# OPEN_SPECTRO_PI_HAT.net
KiCad netlist of a schematic drawn in EAGLE
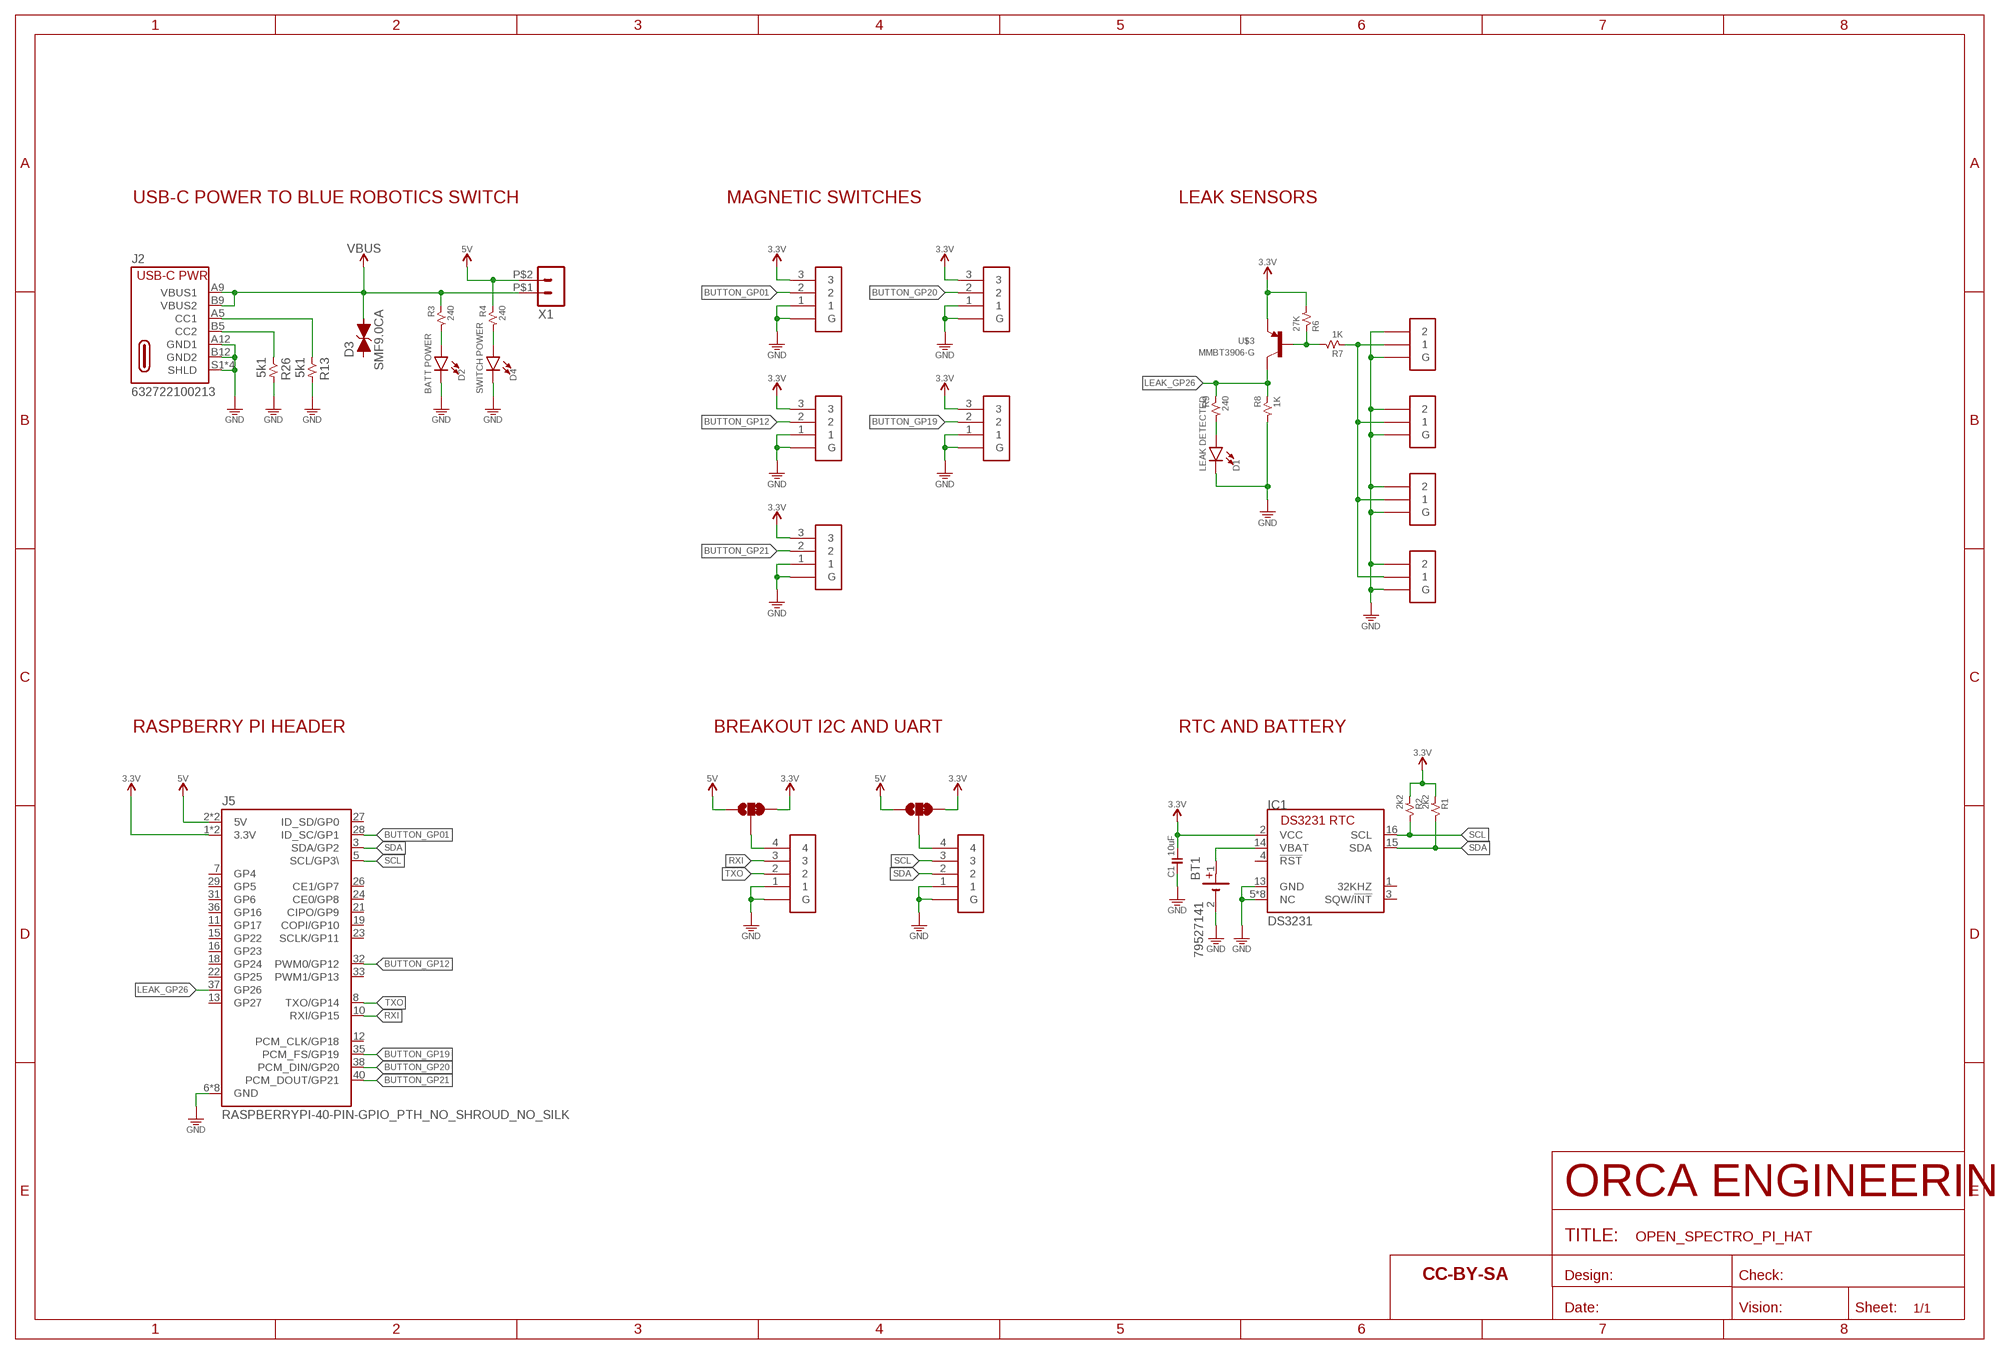
[diagram p0: schematic, sheet 1]

(export (version "E")
  (design (tool "Eeschema 10.0.6"))
  (components
    (comp (ref "BT1")
      (value "79527141")
      (footprint "eagle-import:79527141")
      (fields
        (field (name "DIGIKEY_PART_NO") "732-12325-2-ND")
        (field (name "MANUFACTURER") "Wurth Electronics Inc.")
        (field (name "CREATED_BY") "PCBLayout.com")
      )
      (libsource (lib "eagle-import") (part "79527141"))
    )
    (comp (ref "C1")
      (value "10uF")
      (footprint "eagle-import:0805")
      (libsource (lib "eagle-import") (part "0805"))
    )
    (comp (ref "D1")
      (value "LEAK DETECTED")
      (footprint "eagle-import:0805_LED")
      (libsource (lib "eagle-import") (part "LED0805"))
    )
    (comp (ref "D2")
      (value "BATT POWER")
      (footprint "eagle-import:0805_LED")
      (libsource (lib "eagle-import") (part "LED0805"))
    )
    (comp (ref "D3")
      (value "SMF9.0CA")
      (footprint "eagle-import:SOD-123F-TVS")
      (libsource (lib "eagle-import") (part "DIODE-TVS-BIDIRECTIONALSMF18CA"))
    )
    (comp (ref "D4")
      (value "SWITCH POWER")
      (footprint "eagle-import:0805_LED")
      (libsource (lib "eagle-import") (part "LED0805"))
    )
    (comp (ref "IC1")
      (value "DS3231/SO")
      (footprint "eagle-import:SO16W")
      (libsource (lib "eagle-import") (part "DS3231/SO"))
    )
    (comp (ref "J2")
      (value "632722100213")
      (footprint "eagle-import:632722100213")
      (libsource (lib "eagle-import") (part "USB-C_PWR_6_PIN"))
    )
    (comp (ref "J5")
      (value "RASPBERRYPI-40-PIN-GPIO_PTH_NO_SHROUD_NO_SILK")
      (footprint "eagle-import:2X20_NOSILK")
      (libsource (lib "eagle-import") (part "RASPBERRYPI-40-PIN-GPIO_PTH_NO_SHROUD_NO_SILK"))
    )
    (comp (ref "JP1")
      (value "JUMPER-SMT_3_1-NC_TRACE_SILK")
      (footprint "eagle-import:SMT-JUMPER_3_1-NC_TRACE_SILK")
      (libsource (lib "eagle-import") (part "JUMPER-SMT_3_1-NC_TRACE_SILK"))
    )
    (comp (ref "JP2")
      (value "JUMPER-SMT_3_1-NC_TRACE_SILK")
      (footprint "eagle-import:SMT-JUMPER_3_1-NC_TRACE_SILK")
      (libsource (lib "eagle-import") (part "JUMPER-SMT_3_1-NC_TRACE_SILK"))
    )
    (comp (ref "R1")
      (value "2k2")
      (footprint "eagle-import:0805")
      (libsource (lib "eagle-import") (part "_L_Resistors_vf.673Dwt_LQuWdsXra6AjxcA_0805"))
    )
    (comp (ref "R2")
      (value "2k2")
      (footprint "eagle-import:0805")
      (libsource (lib "eagle-import") (part "_L_Resistors_vf.673Dwt_LQuWdsXra6AjxcA_0805"))
    )
    (comp (ref "R3")
      (value "240")
      (footprint "eagle-import:0805")
      (libsource (lib "eagle-import") (part "_L_Resistors_vf.673Dwt_LQuWdsXra6AjxcA_0805"))
    )
    (comp (ref "R4")
      (value "240")
      (footprint "eagle-import:0805")
      (libsource (lib "eagle-import") (part "_L_Resistors_vf.673Dwt_LQuWdsXra6AjxcA_0805"))
    )
    (comp (ref "R6")
      (value "27K")
      (footprint "eagle-import:0805")
      (libsource (lib "eagle-import") (part "_L_Resistors_vf.673Dwt_LQuWdsXra6AjxcA_0805"))
    )
    (comp (ref "R7")
      (value "1K")
      (footprint "eagle-import:0805")
      (libsource (lib "eagle-import") (part "_L_Resistors_vf.673Dwt_LQuWdsXra6AjxcA_0805"))
    )
    (comp (ref "R8")
      (value "1K")
      (footprint "eagle-import:0805")
      (libsource (lib "eagle-import") (part "_L_Resistors_vf.673Dwt_LQuWdsXra6AjxcA_0805"))
    )
    (comp (ref "R9")
      (value "240")
      (footprint "eagle-import:0805")
      (libsource (lib "eagle-import") (part "_L_Resistors_vf.673Dwt_LQuWdsXra6AjxcA_0805"))
    )
    (comp (ref "R13")
      (value "5k1")
      (footprint "eagle-import:0805")
      (libsource (lib "eagle-import") (part "_L_Resistors_vf.673Dwt_LQuWdsXra6AjxcA_0805"))
    )
    (comp (ref "R26")
      (value "5k1")
      (footprint "eagle-import:0805")
      (libsource (lib "eagle-import") (part "_L_Resistors_vf.673Dwt_LQuWdsXra6AjxcA_0805"))
    )
    (comp (ref "U$1")
      (value "JST-GH-2SIDE")
      (footprint "eagle-import:JST-GH-SIDE-2")
      (libsource (lib "eagle-import") (part "JST-GH-2SIDE"))
    )
    (comp (ref "U$2")
      (value "JST-GH-2SIDE")
      (footprint "eagle-import:JST-GH-SIDE-2")
      (libsource (lib "eagle-import") (part "JST-GH-2SIDE"))
    )
    (comp (ref "U$3")
      (value "MMBT3906-G")
      (footprint "eagle-import:SOT23-3_GENERIC")
      (libsource (lib "eagle-import") (part "TRANS_PNPMMBT3906-G"))
    )
    (comp (ref "U$4")
      (value "JST-GH-3SIDE")
      (footprint "eagle-import:JST-GH-SIDE-3")
      (libsource (lib "eagle-import") (part "JST-GH-3SIDE"))
    )
    (comp (ref "U$5")
      (value "JST-GH-2SIDE")
      (footprint "eagle-import:JST-GH-SIDE-2")
      (libsource (lib "eagle-import") (part "JST-GH-2SIDE"))
    )
    (comp (ref "U$6")
      (value "JST-GH-2SIDE")
      (footprint "eagle-import:JST-GH-SIDE-2")
      (libsource (lib "eagle-import") (part "JST-GH-2SIDE"))
    )
    (comp (ref "U$7")
      (value "JST-GH-4SIDE")
      (footprint "eagle-import:JST-GH-SIDE-4")
      (libsource (lib "eagle-import") (part "JST-GH-4SIDE"))
    )
    (comp (ref "U$8")
      (value "JST-GH-4SIDE")
      (footprint "eagle-import:JST-GH-SIDE-4")
      (libsource (lib "eagle-import") (part "JST-GH-4SIDE"))
    )
    (comp (ref "U$11")
      (value "JST-GH-3SIDE")
      (footprint "eagle-import:JST-GH-SIDE-3")
      (libsource (lib "eagle-import") (part "JST-GH-3SIDE"))
    )
    (comp (ref "U$12")
      (value "JST-GH-3SIDE")
      (footprint "eagle-import:JST-GH-SIDE-3")
      (libsource (lib "eagle-import") (part "JST-GH-3SIDE"))
    )
    (comp (ref "U$14")
      (value "JST-GH-3SIDE")
      (footprint "eagle-import:JST-GH-SIDE-3")
      (libsource (lib "eagle-import") (part "JST-GH-3SIDE"))
    )
    (comp (ref "U$15")
      (value "JST-GH-3SIDE")
      (footprint "eagle-import:JST-GH-SIDE-3")
      (libsource (lib "eagle-import") (part "JST-GH-3SIDE"))
    )
    (comp (ref "X1")
      (value "MICRO-FIT_02P43650-0200")
      (footprint "eagle-import:43650-0200")
      (libsource (lib "eagle-import") (part "MICRO-FIT_02P43650-0200"))
    )
  )
  (nets
    (net (code "1") (name "3.3V") (class "Default")
      (node (ref "C1") (pin "1") (pinfunction "1_1") (pintype "passive"))
      (node (ref "IC1") (pin "2") (pinfunction "VCC_2") (pintype "power_in"))
      (node (ref "J5") (pin "1") (pinfunction "3.3V_1") (pintype "power_in"))
      (node (ref "J5") (pin "17") (pinfunction "3.3V_17") (pintype "power_in"))
      (node (ref "JP1") (pin "3") (pinfunction "3_3") (pintype "passive"))
      (node (ref "JP2") (pin "3") (pinfunction "3_3") (pintype "passive"))
      (node (ref "R1") (pin "2") (pinfunction "2_2") (pintype "passive"))
      (node (ref "R2") (pin "2") (pinfunction "2_2") (pintype "passive"))
      (node (ref "R6") (pin "2") (pinfunction "2_2") (pintype "passive"))
      (node (ref "U$11") (pin "3") (pinfunction "3_3") (pintype "bidirectional"))
      (node (ref "U$12") (pin "3") (pinfunction "3_3") (pintype "bidirectional"))
      (node (ref "U$14") (pin "3") (pinfunction "3_3") (pintype "bidirectional"))
      (node (ref "U$15") (pin "3") (pinfunction "3_3") (pintype "bidirectional"))
      (node (ref "U$3") (pin "3") (pinfunction "C_3") (pintype "passive"))
      (node (ref "U$4") (pin "3") (pinfunction "3_3") (pintype "bidirectional"))
    )
    (net (code "2") (name "5V") (class "Default")
      (node (ref "J5") (pin "2") (pinfunction "5V_2") (pintype "power_in"))
      (node (ref "J5") (pin "4") (pinfunction "5V_4") (pintype "power_in"))
      (node (ref "JP1") (pin "1") (pinfunction "1_1") (pintype "passive"))
      (node (ref "JP2") (pin "1") (pinfunction "1_1") (pintype "passive"))
      (node (ref "R4") (pin "1") (pinfunction "1_1") (pintype "passive"))
      (node (ref "X1") (pin "P$2") (pinfunction "2_P$2") (pintype "passive"))
    )
    (net (code "3") (name "BUTTON_GP01") (class "Default")
      (node (ref "J5") (pin "28") (pinfunction "ID_SC/GP1_28") (pintype "bidirectional"))
      (node (ref "U$4") (pin "2") (pinfunction "2_2") (pintype "bidirectional"))
    )
    (net (code "4") (name "BUTTON_GP12") (class "Default")
      (node (ref "J5") (pin "32") (pinfunction "PWM0/GP12_32") (pintype "bidirectional"))
      (node (ref "U$11") (pin "2") (pinfunction "2_2") (pintype "bidirectional"))
    )
    (net (code "5") (name "BUTTON_GP19") (class "Default")
      (node (ref "J5") (pin "35") (pinfunction "PCM_FS/GP19_35") (pintype "bidirectional"))
      (node (ref "U$15") (pin "2") (pinfunction "2_2") (pintype "bidirectional"))
    )
    (net (code "6") (name "BUTTON_GP20") (class "Default")
      (node (ref "J5") (pin "38") (pinfunction "PCM_DIN/GP20_38") (pintype "bidirectional"))
      (node (ref "U$14") (pin "2") (pinfunction "2_2") (pintype "bidirectional"))
    )
    (net (code "7") (name "BUTTON_GP21") (class "Default")
      (node (ref "J5") (pin "40") (pinfunction "PCM_DOUT/GP21_40") (pintype "bidirectional"))
      (node (ref "U$12") (pin "2") (pinfunction "2_2") (pintype "bidirectional"))
    )
    (net (code "8") (name "GND") (class "Default")
      (node (ref "BT1") (pin "2") (pinfunction "-_2") (pintype "passive"))
      (node (ref "C1") (pin "2") (pinfunction "2_2") (pintype "passive"))
      (node (ref "D1") (pin "C") (pinfunction "C_C") (pintype "passive"))
      (node (ref "D2") (pin "C") (pinfunction "C_C") (pintype "passive"))
      (node (ref "D4") (pin "C") (pinfunction "C_C") (pintype "passive"))
      (node (ref "IC1") (pin "10") (pinfunction "NC_10") (pintype "power_in"))
      (node (ref "IC1") (pin "11") (pinfunction "NC_11") (pintype "power_in"))
      (node (ref "IC1") (pin "12") (pinfunction "NC_12") (pintype "power_in"))
      (node (ref "IC1") (pin "13") (pinfunction "GND_13") (pintype "power_in"))
      (node (ref "IC1") (pin "5") (pinfunction "NC_5") (pintype "power_in"))
      (node (ref "IC1") (pin "6") (pinfunction "NC_6") (pintype "power_in"))
      (node (ref "IC1") (pin "7") (pinfunction "NC_7") (pintype "power_in"))
      (node (ref "IC1") (pin "8") (pinfunction "NC_8") (pintype "power_in"))
      (node (ref "IC1") (pin "9") (pinfunction "NC_9") (pintype "power_in"))
      (node (ref "J2") (pin "A12") (pinfunction "GND1_A12") (pintype "passive"))
      (node (ref "J2") (pin "B12") (pinfunction "GND2_B12") (pintype "passive"))
      (node (ref "J2") (pin "S1") (pinfunction "SHLD_S1") (pintype "passive"))
      (node (ref "J2") (pin "S2") (pinfunction "SHLD_S2") (pintype "passive"))
      (node (ref "J2") (pin "S3") (pinfunction "SHLD_S3") (pintype "passive"))
      (node (ref "J2") (pin "S4") (pinfunction "SHLD_S4") (pintype "passive"))
      (node (ref "J5") (pin "14") (pinfunction "GND_14") (pintype "power_in"))
      (node (ref "J5") (pin "20") (pinfunction "GND_20") (pintype "power_in"))
      (node (ref "J5") (pin "25") (pinfunction "GND_25") (pintype "power_in"))
      (node (ref "J5") (pin "30") (pinfunction "GND_30") (pintype "power_in"))
      (node (ref "J5") (pin "34") (pinfunction "GND_34") (pintype "power_in"))
      (node (ref "J5") (pin "39") (pinfunction "GND_39") (pintype "power_in"))
      (node (ref "J5") (pin "6") (pinfunction "GND_6") (pintype "power_in"))
      (node (ref "J5") (pin "9") (pinfunction "GND_9") (pintype "power_in"))
      (node (ref "R13") (pin "2") (pinfunction "2_2") (pintype "passive"))
      (node (ref "R26") (pin "2") (pinfunction "2_2") (pintype "passive"))
      (node (ref "R8") (pin "2") (pinfunction "2_2") (pintype "passive"))
      (node (ref "U$1") (pin "2") (pinfunction "2_2") (pintype "bidirectional"))
      (node (ref "U$1") (pin "MECH1") (pinfunction "G_MECH1") (pintype "bidirectional"))
      (node (ref "U$1") (pin "MECH2") (pinfunction "G_MECH2") (pintype "bidirectional"))
      (node (ref "U$11") (pin "1") (pinfunction "1_1") (pintype "bidirectional"))
      (node (ref "U$11") (pin "MECH1") (pinfunction "G_MECH1") (pintype "bidirectional"))
      (node (ref "U$11") (pin "MECH2") (pinfunction "G_MECH2") (pintype "bidirectional"))
      (node (ref "U$12") (pin "1") (pinfunction "1_1") (pintype "bidirectional"))
      (node (ref "U$12") (pin "MECH1") (pinfunction "G_MECH1") (pintype "bidirectional"))
      (node (ref "U$12") (pin "MECH2") (pinfunction "G_MECH2") (pintype "bidirectional"))
      (node (ref "U$14") (pin "1") (pinfunction "1_1") (pintype "bidirectional"))
      (node (ref "U$14") (pin "MECH1") (pinfunction "G_MECH1") (pintype "bidirectional"))
      (node (ref "U$14") (pin "MECH2") (pinfunction "G_MECH2") (pintype "bidirectional"))
      (node (ref "U$15") (pin "1") (pinfunction "1_1") (pintype "bidirectional"))
      (node (ref "U$15") (pin "MECH1") (pinfunction "G_MECH1") (pintype "bidirectional"))
      (node (ref "U$15") (pin "MECH2") (pinfunction "G_MECH2") (pintype "bidirectional"))
      (node (ref "U$2") (pin "2") (pinfunction "2_2") (pintype "bidirectional"))
      (node (ref "U$2") (pin "MECH1") (pinfunction "G_MECH1") (pintype "bidirectional"))
      (node (ref "U$2") (pin "MECH2") (pinfunction "G_MECH2") (pintype "bidirectional"))
      (node (ref "U$4") (pin "1") (pinfunction "1_1") (pintype "bidirectional"))
      (node (ref "U$4") (pin "MECH1") (pinfunction "G_MECH1") (pintype "bidirectional"))
      (node (ref "U$4") (pin "MECH2") (pinfunction "G_MECH2") (pintype "bidirectional"))
      (node (ref "U$5") (pin "2") (pinfunction "2_2") (pintype "bidirectional"))
      (node (ref "U$5") (pin "MECH1") (pinfunction "G_MECH1") (pintype "bidirectional"))
      (node (ref "U$5") (pin "MECH2") (pinfunction "G_MECH2") (pintype "bidirectional"))
      (node (ref "U$6") (pin "2") (pinfunction "2_2") (pintype "bidirectional"))
      (node (ref "U$6") (pin "MECH1") (pinfunction "G_MECH1") (pintype "bidirectional"))
      (node (ref "U$6") (pin "MECH2") (pinfunction "G_MECH2") (pintype "bidirectional"))
      (node (ref "U$7") (pin "1") (pinfunction "1_1") (pintype "bidirectional"))
      (node (ref "U$7") (pin "MECH1") (pinfunction "G_MECH1") (pintype "bidirectional"))
      (node (ref "U$7") (pin "MECH2") (pinfunction "G_MECH2") (pintype "bidirectional"))
      (node (ref "U$8") (pin "1") (pinfunction "1_1") (pintype "bidirectional"))
      (node (ref "U$8") (pin "MECH1") (pinfunction "G_MECH1") (pintype "bidirectional"))
      (node (ref "U$8") (pin "MECH2") (pinfunction "G_MECH2") (pintype "bidirectional"))
    )
    (net (code "9") (name "LEAK_GP26") (class "Default")
      (node (ref "J5") (pin "37") (pinfunction "GP26_37") (pintype "bidirectional"))
      (node (ref "R8") (pin "1") (pinfunction "1_1") (pintype "passive"))
      (node (ref "R9") (pin "1") (pinfunction "1_1") (pintype "passive"))
      (node (ref "U$3") (pin "2") (pinfunction "E_2") (pintype "passive"))
    )
    (net (code "10") (name "Net-(BT1-+)") (class "Default")
      (node (ref "BT1") (pin "1") (pinfunction "+_1") (pintype "passive"))
      (node (ref "IC1") (pin "14") (pinfunction "VBAT_14") (pintype "power_in"))
    )
    (net (code "11") (name "Net-(D1-PadA)") (class "Default")
      (node (ref "D1") (pin "A") (pinfunction "A_A") (pintype "passive"))
      (node (ref "R9") (pin "2") (pinfunction "2_2") (pintype "passive"))
    )
    (net (code "12") (name "Net-(D2-PadA)") (class "Default")
      (node (ref "D2") (pin "A") (pinfunction "A_A") (pintype "passive"))
      (node (ref "R3") (pin "2") (pinfunction "2_2") (pintype "passive"))
    )
    (net (code "13") (name "Net-(D4-PadA)") (class "Default")
      (node (ref "D4") (pin "A") (pinfunction "A_A") (pintype "passive"))
      (node (ref "R4") (pin "2") (pinfunction "2_2") (pintype "passive"))
    )
    (net (code "14") (name "Net-(J2-CC1)") (class "Default")
      (node (ref "J2") (pin "A5") (pinfunction "CC1_A5") (pintype "passive"))
      (node (ref "R13") (pin "1") (pinfunction "1_1") (pintype "passive"))
    )
    (net (code "15") (name "Net-(J2-CC2)") (class "Default")
      (node (ref "J2") (pin "B5") (pinfunction "CC2_B5") (pintype "passive"))
      (node (ref "R26") (pin "1") (pinfunction "1_1") (pintype "passive"))
    )
    (net (code "16") (name "Net-(JP1-Pad2)") (class "Default")
      (node (ref "JP1") (pin "2") (pinfunction "2_2") (pintype "passive"))
      (node (ref "U$7") (pin "4") (pinfunction "4_4") (pintype "bidirectional"))
    )
    (net (code "17") (name "Net-(JP2-Pad2)") (class "Default")
      (node (ref "JP2") (pin "2") (pinfunction "2_2") (pintype "passive"))
      (node (ref "U$8") (pin "4") (pinfunction "4_4") (pintype "bidirectional"))
    )
    (net (code "18") (name "Net-(R7-Pad2)") (class "Default")
      (node (ref "R7") (pin "2") (pinfunction "2_2") (pintype "passive"))
      (node (ref "U$1") (pin "1") (pinfunction "1_1") (pintype "bidirectional"))
      (node (ref "U$2") (pin "1") (pinfunction "1_1") (pintype "bidirectional"))
      (node (ref "U$5") (pin "1") (pinfunction "1_1") (pintype "bidirectional"))
      (node (ref "U$6") (pin "1") (pinfunction "1_1") (pintype "bidirectional"))
    )
    (net (code "19") (name "Net-(U$3-B)") (class "Default")
      (node (ref "R6") (pin "1") (pinfunction "1_1") (pintype "passive"))
      (node (ref "R7") (pin "1") (pinfunction "1_1") (pintype "passive"))
      (node (ref "U$3") (pin "1") (pinfunction "B_1") (pintype "passive"))
    )
    (net (code "20") (name "RXI") (class "Default")
      (node (ref "J5") (pin "10") (pinfunction "RXI/GP15_10") (pintype "input"))
      (node (ref "U$8") (pin "3") (pinfunction "3_3") (pintype "bidirectional"))
    )
    (net (code "21") (name "SCL") (class "Default")
      (node (ref "IC1") (pin "16") (pinfunction "SCL_16") (pintype "bidirectional"))
      (node (ref "J5") (pin "5") (pinfunction "SCL/GP3\\_5") (pintype "bidirectional"))
      (node (ref "R2") (pin "1") (pinfunction "1_1") (pintype "passive"))
      (node (ref "U$7") (pin "3") (pinfunction "3_3") (pintype "bidirectional"))
    )
    (net (code "22") (name "SDA") (class "Default")
      (node (ref "IC1") (pin "15") (pinfunction "SDA_15") (pintype "bidirectional"))
      (node (ref "J5") (pin "3") (pinfunction "SDA/GP2_3") (pintype "bidirectional"))
      (node (ref "R1") (pin "1") (pinfunction "1_1") (pintype "passive"))
      (node (ref "U$7") (pin "2") (pinfunction "2_2") (pintype "bidirectional"))
    )
    (net (code "23") (name "TXO") (class "Default")
      (node (ref "J5") (pin "8") (pinfunction "TXO/GP14_8") (pintype "output"))
      (node (ref "U$8") (pin "2") (pinfunction "2_2") (pintype "bidirectional"))
    )
    (net (code "24") (name "VBUS") (class "Default")
      (node (ref "D3") (pin "C") (pinfunction "C2_C") (pintype "passive"))
      (node (ref "J2") (pin "A9") (pinfunction "VBUS1_A9") (pintype "passive"))
      (node (ref "J2") (pin "B9") (pinfunction "VBUS2_B9") (pintype "passive"))
      (node (ref "R3") (pin "1") (pinfunction "1_1") (pintype "passive"))
      (node (ref "X1") (pin "P$1") (pinfunction "1_P$1") (pintype "passive"))
    )
    (net (code "25") (name "unconnected-(D3-C1-PadA)") (class "Default")
      (node (ref "D3") (pin "A") (pinfunction "C1_A") (pintype "passive"))
    )
    (net (code "26") (name "unconnected-(IC1-32KHZ-Pad1)") (class "Default")
      (node (ref "IC1") (pin "1") (pinfunction "32KHZ_1") (pintype "output"))
    )
    (net (code "27") (name "unconnected-(IC1-SQW{slash}~{INT}-Pad3)") (class "Default")
      (node (ref "IC1") (pin "3") (pinfunction "SQW/~{INT}_3") (pintype "output"))
    )
    (net (code "28") (name "unconnected-(IC1-~{RST}-Pad4)") (class "Default")
      (node (ref "IC1") (pin "4") (pinfunction "~{RST}_4") (pintype "bidirectional"))
    )
    (net (code "29") (name "unconnected-(J5-CE0{slash}GP8-Pad24)") (class "Default")
      (node (ref "J5") (pin "24") (pinfunction "CE0/GP8_24") (pintype "output"))
    )
    (net (code "30") (name "unconnected-(J5-CE1{slash}GP7-Pad26)") (class "Default")
      (node (ref "J5") (pin "26") (pinfunction "CE1/GP7_26") (pintype "output"))
    )
    (net (code "31") (name "unconnected-(J5-CIPO{slash}GP9-Pad21)") (class "Default")
      (node (ref "J5") (pin "21") (pinfunction "CIPO/GP9_21") (pintype "input"))
    )
    (net (code "32") (name "unconnected-(J5-COPI{slash}GP10-Pad19)") (class "Default")
      (node (ref "J5") (pin "19") (pinfunction "COPI/GP10_19") (pintype "output"))
    )
    (net (code "33") (name "unconnected-(J5-GP4-Pad7)") (class "Default")
      (node (ref "J5") (pin "7") (pinfunction "GP4_7") (pintype "bidirectional"))
    )
    (net (code "34") (name "unconnected-(J5-GP5-Pad29)") (class "Default")
      (node (ref "J5") (pin "29") (pinfunction "GP5_29") (pintype "bidirectional"))
    )
    (net (code "35") (name "unconnected-(J5-GP6-Pad31)") (class "Default")
      (node (ref "J5") (pin "31") (pinfunction "GP6_31") (pintype "bidirectional"))
    )
    (net (code "36") (name "unconnected-(J5-GP16-Pad36)") (class "Default")
      (node (ref "J5") (pin "36") (pinfunction "GP16_36") (pintype "bidirectional"))
    )
    (net (code "37") (name "unconnected-(J5-GP17-Pad11)") (class "Default")
      (node (ref "J5") (pin "11") (pinfunction "GP17_11") (pintype "bidirectional"))
    )
    (net (code "38") (name "unconnected-(J5-GP22-Pad15)") (class "Default")
      (node (ref "J5") (pin "15") (pinfunction "GP22_15") (pintype "bidirectional"))
    )
    (net (code "39") (name "unconnected-(J5-GP23-Pad16)") (class "Default")
      (node (ref "J5") (pin "16") (pinfunction "GP23_16") (pintype "bidirectional"))
    )
    (net (code "40") (name "unconnected-(J5-GP24-Pad18)") (class "Default")
      (node (ref "J5") (pin "18") (pinfunction "GP24_18") (pintype "bidirectional"))
    )
    (net (code "41") (name "unconnected-(J5-GP25-Pad22)") (class "Default")
      (node (ref "J5") (pin "22") (pinfunction "GP25_22") (pintype "bidirectional"))
    )
    (net (code "42") (name "unconnected-(J5-GP27-Pad13)") (class "Default")
      (node (ref "J5") (pin "13") (pinfunction "GP27_13") (pintype "bidirectional"))
    )
    (net (code "43") (name "unconnected-(J5-ID_SD{slash}GP0-Pad27)") (class "Default")
      (node (ref "J5") (pin "27") (pinfunction "ID_SD/GP0_27") (pintype "bidirectional"))
    )
    (net (code "44") (name "unconnected-(J5-PCM_CLK{slash}GP18-Pad12)") (class "Default")
      (node (ref "J5") (pin "12") (pinfunction "PCM_CLK/GP18_12") (pintype "bidirectional"))
    )
    (net (code "45") (name "unconnected-(J5-PWM1{slash}GP13-Pad33)") (class "Default")
      (node (ref "J5") (pin "33") (pinfunction "PWM1/GP13_33") (pintype "bidirectional"))
    )
    (net (code "46") (name "unconnected-(J5-SCLK{slash}GP11-Pad23)") (class "Default")
      (node (ref "J5") (pin "23") (pinfunction "SCLK/GP11_23") (pintype "output"))
    )
  )
)
